# VER.net
KiCad netlist of a schematic drawn in Altium Designer
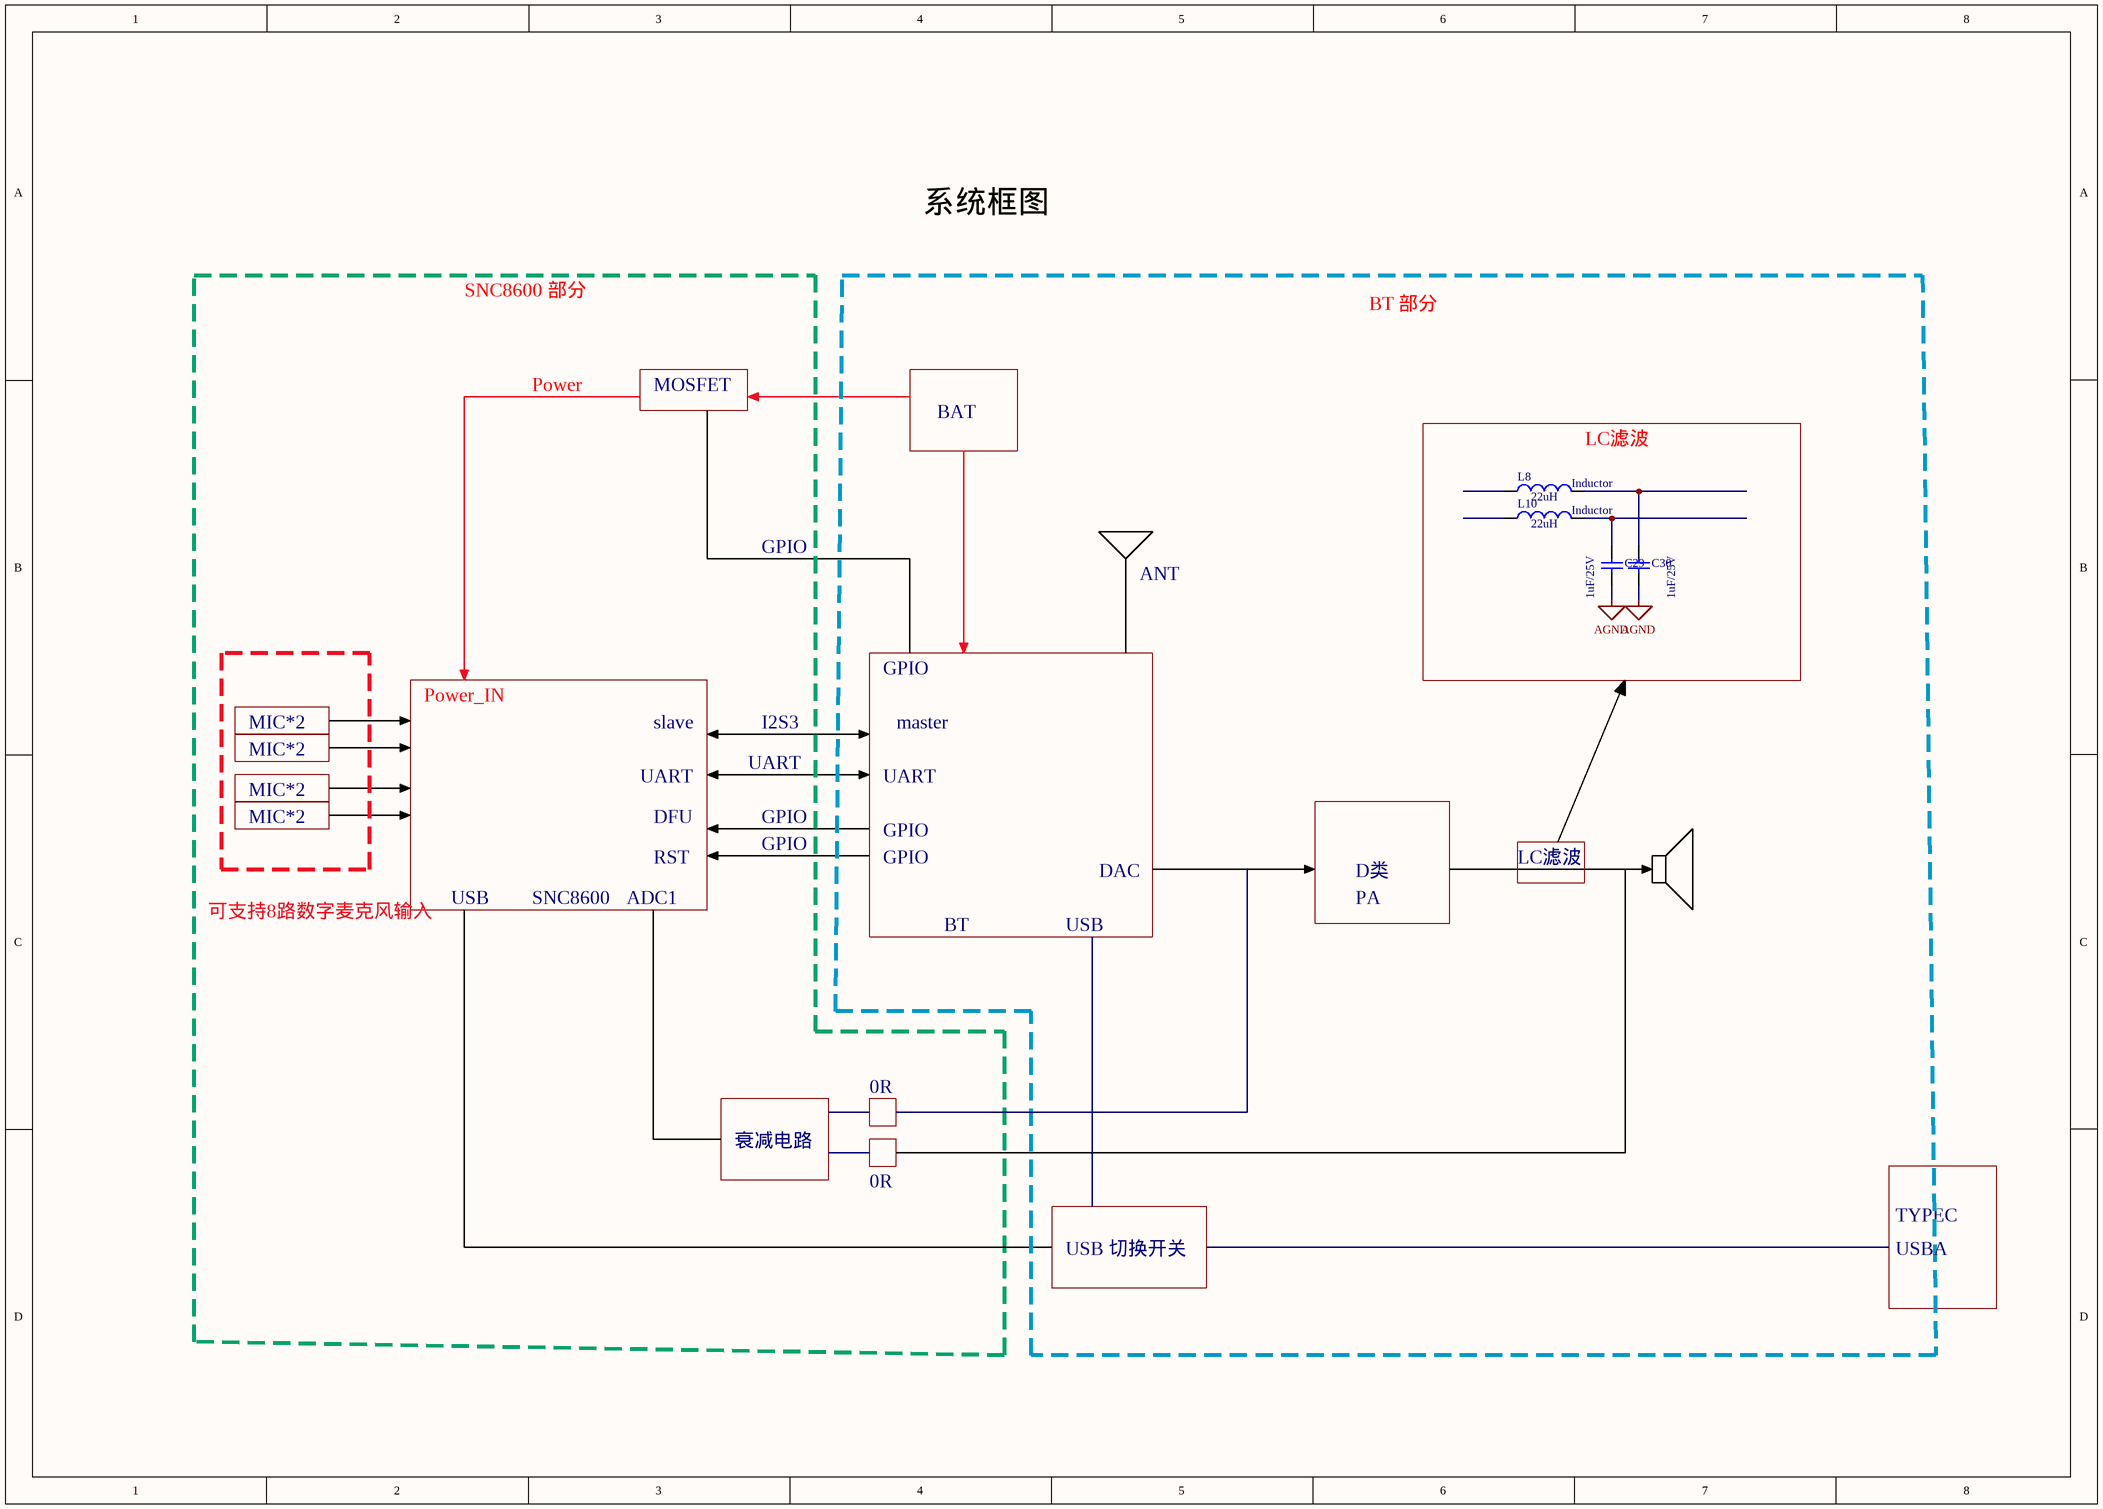
[diagram p0: VER.SchDoc]

(export (version "E")
  (design (tool "Eeschema 10.0.6"))
  (components
    (comp (ref "C29")
      (value "1uF/25V")
      (footprint "C0603")
      (description "Capacitor (Semiconductor SIM Model)")
      (fields (field (name "PUBLISHER") "Altium Limited"))
      (libsource (lib "Miscellaneous Devices") (part "Cap Semi"))
    )
    (comp (ref "C30")
      (value "1uF/25V")
      (footprint "C0603")
      (description "Capacitor (Semiconductor SIM Model)")
      (fields (field (name "PUBLISHER") "Altium Limited"))
      (libsource (lib "Miscellaneous Devices") (part "Cap Semi"))
    )
    (comp (ref "L8")
      (value "Inductor")
      (footprint "0402-A")
      (fields (field (name "ALTIUM_VALUE") "22uH") (field (name "PUBLISHER") "Altium Limited"))
      (libsource (lib "Miscellaneous Devices") (part "Inductor"))
    )
    (comp (ref "L10")
      (value "Inductor")
      (footprint "0402-A")
      (fields (field (name "ALTIUM_VALUE") "22uH") (field (name "PUBLISHER") "Altium Limited"))
      (libsource (lib "Miscellaneous Devices") (part "Inductor"))
    )
  )
  (nets
    (net (code "1") (name "AGND") (class "Default")
      (node (ref "C29") (pin "1") (pinfunction "1_1") (pintype "passive"))
      (node (ref "C30") (pin "1") (pinfunction "1_1") (pintype "passive"))
    )
    (net (code "2") (name "Net-(C29-Pad2)") (class "Default")
      (node (ref "C29") (pin "2") (pinfunction "2_2") (pintype "passive"))
      (node (ref "L10") (pin "2") (pinfunction "2_2") (pintype "passive"))
    )
    (net (code "3") (name "Net-(C30-Pad2)") (class "Default")
      (node (ref "C30") (pin "2") (pinfunction "2_2") (pintype "passive"))
      (node (ref "L8") (pin "2") (pinfunction "2_2") (pintype "passive"))
    )
    (net (code "4") (name "unconnected-(L8-Pad1)") (class "Default")
      (node (ref "L8") (pin "1") (pinfunction "1_1") (pintype "passive"))
    )
    (net (code "5") (name "unconnected-(L10-Pad1)") (class "Default")
      (node (ref "L10") (pin "1") (pinfunction "1_1") (pintype "passive"))
    )
  )
)
